# protoLoad.net
KiCad netlist of a schematic drawn in EAGLE
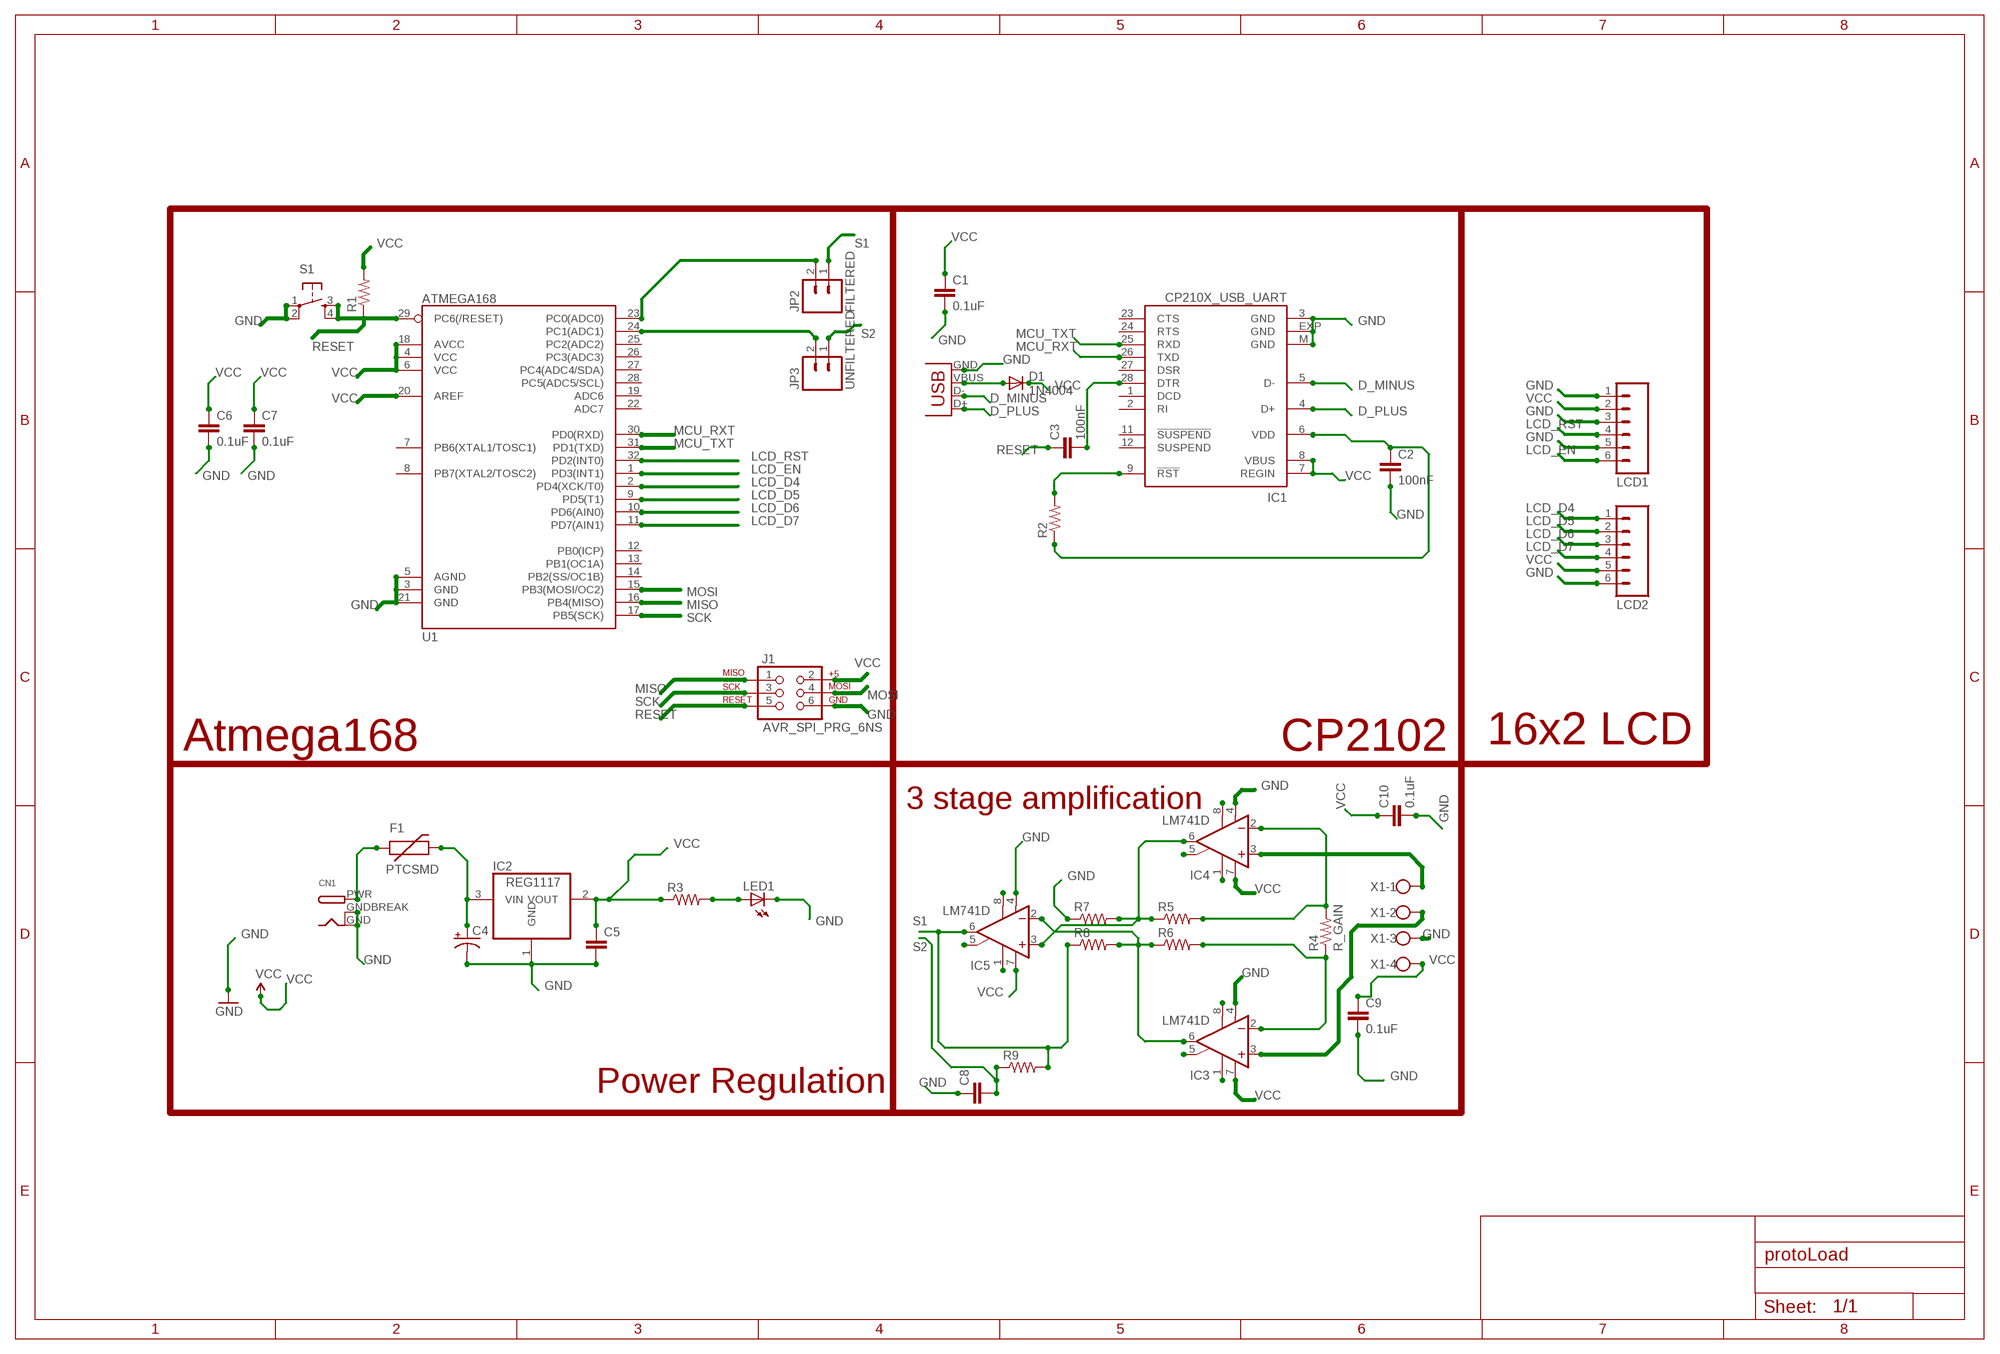
[diagram p0: schematic, sheet 1]

(export (version "E")
  (design (tool "Eeschema 10.0.6"))
  (components
    (comp (ref "C1")
      (value "0.1uF")
      (footprint "eagle-import:0805")
      (libsource (lib "eagle-import") (part "CAP0805"))
    )
    (comp (ref "C2")
      (value "100nF")
      (footprint "eagle-import:0805")
      (libsource (lib "eagle-import") (part "CAP0805"))
    )
    (comp (ref "C3")
      (value "100nF")
      (footprint "eagle-import:0805")
      (libsource (lib "eagle-import") (part "CAP0805"))
    )
    (comp (ref "C4")
      (value "CAP_POL7343")
      (footprint "eagle-import:EIA7343")
      (libsource (lib "eagle-import") (part "CAP_POL7343"))
    )
    (comp (ref "C5")
      (value "CAP0805")
      (footprint "eagle-import:0805")
      (libsource (lib "eagle-import") (part "CAP0805"))
    )
    (comp (ref "C6")
      (value "0.1uF")
      (footprint "eagle-import:0805")
      (libsource (lib "eagle-import") (part "CAP0805"))
    )
    (comp (ref "C7")
      (value "0.1uF")
      (footprint "eagle-import:0805")
      (libsource (lib "eagle-import") (part "CAP0805"))
    )
    (comp (ref "C8")
      (value "CAP0805")
      (footprint "eagle-import:0805")
      (libsource (lib "eagle-import") (part "CAP0805"))
    )
    (comp (ref "C9")
      (value "0.1uF")
      (footprint "eagle-import:0805")
      (libsource (lib "eagle-import") (part "CAP0805"))
    )
    (comp (ref "C10")
      (value "0.1uF")
      (footprint "eagle-import:0805")
      (libsource (lib "eagle-import") (part "CAP0805"))
    )
    (comp (ref "CN1")
      (value "DCBARRELPTH")
      (footprint "eagle-import:DCJACK_2MM_PTH")
      (libsource (lib "eagle-import") (part "DCBARRELPTH"))
    )
    (comp (ref "D1")
      (value "1N4004")
      (footprint "eagle-import:SMA-DIODE_ALT")
      (libsource (lib "eagle-import") (part "DIODESMA-ALT"))
    )
    (comp (ref "F1")
      (value "PTCSMD")
      (footprint "eagle-import:PTC-1206")
      (libsource (lib "eagle-import") (part "PTCSMD"))
    )
    (comp (ref "IC1")
      (value "CP210X_USB_UART")
      (footprint "eagle-import:MLP28")
      (libsource (lib "eagle-import") (part "CP210X_USB_UART"))
    )
    (comp (ref "IC2")
      (value "REG1117")
      (footprint "eagle-import:SOT223")
      (libsource (lib "eagle-import") (part "REG1117"))
    )
    (comp (ref "IC3")
      (value "LM741D")
      (footprint "eagle-import:SO08")
      (libsource (lib "eagle-import") (part "741DLM"))
    )
    (comp (ref "IC4")
      (value "LM741D")
      (footprint "eagle-import:SO08")
      (libsource (lib "eagle-import") (part "741DLM"))
    )
    (comp (ref "IC5")
      (value "LM741D")
      (footprint "eagle-import:SO08")
      (libsource (lib "eagle-import") (part "741DLM"))
    )
    (comp (ref "J1")
      (value "AVR_SPI_PRG_6NS")
      (footprint "eagle-import:2X3-NS")
      (libsource (lib "eagle-import") (part "AVR_SPI_PRG_6NS"))
    )
    (comp (ref "JP1")
      (value "USBSMD")
      (footprint "eagle-import:USB-MINIB")
      (libsource (lib "eagle-import") (part "USBSMD"))
    )
    (comp (ref "JP2")
      (value "FILTERED")
      (footprint "eagle-import:1X02_LONGPADS")
      (libsource (lib "eagle-import") (part "M02PTH3"))
    )
    (comp (ref "JP3")
      (value "UNFILTERED")
      (footprint "eagle-import:1X02_LONGPADS")
      (libsource (lib "eagle-import") (part "M02PTH3"))
    )
    (comp (ref "LCD1")
      (value "M06LONGPADS")
      (footprint "eagle-import:1X06_LONGPADS")
      (libsource (lib "eagle-import") (part "M06LONGPADS"))
    )
    (comp (ref "LCD2")
      (value "M06LONGPADS")
      (footprint "eagle-import:1X06_LONGPADS")
      (libsource (lib "eagle-import") (part "M06LONGPADS"))
    )
    (comp (ref "LED1")
      (value "LEDCHIPLED_1206")
      (footprint "eagle-import:CHIPLED_1206")
      (libsource (lib "eagle-import") (part "LEDCHIPLED_1206"))
    )
    (comp (ref "R1")
      (value "RESISTOR0805-RES")
      (footprint "eagle-import:0805")
      (libsource (lib "eagle-import") (part "SparkFun-Resistors_RESISTOR0805-RES"))
    )
    (comp (ref "R2")
      (value "RESISTOR0805-RES")
      (footprint "eagle-import:0805")
      (libsource (lib "eagle-import") (part "RESISTOR0805-RES"))
    )
    (comp (ref "R3")
      (value "RESISTOR0805-RES")
      (footprint "eagle-import:0805")
      (libsource (lib "eagle-import") (part "SparkFun-Resistors_RESISTOR0805-RES"))
    )
    (comp (ref "R4")
      (value "R_GAIN")
      (footprint "eagle-import:0805")
      (libsource (lib "eagle-import") (part "SparkFun-Resistors_RESISTOR0805-RES"))
    )
    (comp (ref "R5")
      (value "RESISTOR0805-RES")
      (footprint "eagle-import:0805")
      (libsource (lib "eagle-import") (part "SparkFun-Resistors_RESISTOR0805-RES"))
    )
    (comp (ref "R6")
      (value "RESISTOR0805-RES")
      (footprint "eagle-import:0805")
      (libsource (lib "eagle-import") (part "SparkFun-Resistors_RESISTOR0805-RES"))
    )
    (comp (ref "R7")
      (value "RESISTOR0805-RES")
      (footprint "eagle-import:0805")
      (libsource (lib "eagle-import") (part "SparkFun-Resistors_RESISTOR0805-RES"))
    )
    (comp (ref "R8")
      (value "RESISTOR0805-RES")
      (footprint "eagle-import:0805")
      (libsource (lib "eagle-import") (part "SparkFun-Resistors_RESISTOR0805-RES"))
    )
    (comp (ref "R9")
      (value "RESISTOR0805-RES")
      (footprint "eagle-import:0805")
      (libsource (lib "eagle-import") (part "SparkFun-Resistors_RESISTOR0805-RES"))
    )
    (comp (ref "S1")
      (value "TAC_SWITCHSMD")
      (footprint "eagle-import:TACTILE_SWITCH_SMD")
      (libsource (lib "eagle-import") (part "TAC_SWITCHSMD"))
    )
    (comp (ref "U1")
      (value "ATMEGA168")
      (footprint "eagle-import:TQFP32-08")
      (libsource (lib "eagle-import") (part "ATMEGA168"))
    )
    (comp (ref "X1")
      (value "W237-4")
      (footprint "eagle-import:W237-4")
      (libsource (lib "eagle-import") (part "W237-4"))
    )
  )
  (nets
    (net (code "1") (name "/D_MINUS") (class "Default")
      (node (ref "IC1") (pin "5") (pinfunction "D-_5") (pintype "bidirectional"))
      (node (ref "JP1") (pin "D-") (pinfunction "D-_D-") (pintype "bidirectional"))
    )
    (net (code "2") (name "/D_PLUS") (class "Default")
      (node (ref "IC1") (pin "4") (pinfunction "D+_4") (pintype "bidirectional"))
      (node (ref "JP1") (pin "D+") (pinfunction "D+_D+") (pintype "bidirectional"))
    )
    (net (code "3") (name "/LCD_D4") (class "Default")
      (node (ref "LCD2") (pin "1") (pinfunction "1_1") (pintype "passive"))
      (node (ref "U1") (pin "2") (pinfunction "PD4(XCK/T0)_2") (pintype "bidirectional"))
    )
    (net (code "4") (name "/LCD_D5") (class "Default")
      (node (ref "LCD2") (pin "2") (pinfunction "2_2") (pintype "passive"))
      (node (ref "U1") (pin "9") (pinfunction "PD5(T1)_9") (pintype "bidirectional"))
    )
    (net (code "5") (name "/LCD_D6") (class "Default")
      (node (ref "LCD2") (pin "3") (pinfunction "3_3") (pintype "passive"))
      (node (ref "U1") (pin "10") (pinfunction "PD6(AIN0)_10") (pintype "bidirectional"))
    )
    (net (code "6") (name "/LCD_D7") (class "Default")
      (node (ref "LCD2") (pin "4") (pinfunction "4_4") (pintype "passive"))
      (node (ref "U1") (pin "11") (pinfunction "PD7(AIN1)_11") (pintype "bidirectional"))
    )
    (net (code "7") (name "/LCD_EN") (class "Default")
      (node (ref "LCD1") (pin "6") (pinfunction "6_6") (pintype "passive"))
      (node (ref "U1") (pin "1") (pinfunction "PD3(INT1)_1") (pintype "bidirectional"))
    )
    (net (code "8") (name "/LCD_RST") (class "Default")
      (node (ref "LCD1") (pin "4") (pinfunction "4_4") (pintype "passive"))
      (node (ref "U1") (pin "32") (pinfunction "PD2(INT0)_32") (pintype "bidirectional"))
    )
    (net (code "9") (name "/MCU_RXT") (class "Default")
      (node (ref "IC1") (pin "26") (pinfunction "TXD_26") (pintype "output"))
      (node (ref "U1") (pin "30") (pinfunction "PD0(RXD)_30") (pintype "bidirectional"))
    )
    (net (code "10") (name "/MCU_TXT") (class "Default")
      (node (ref "IC1") (pin "25") (pinfunction "RXD_25") (pintype "input"))
      (node (ref "U1") (pin "31") (pinfunction "PD1(TXD)_31") (pintype "bidirectional"))
    )
    (net (code "11") (name "/MISO") (class "Default")
      (node (ref "J1") (pin "1") (pinfunction "1_1") (pintype "passive"))
      (node (ref "U1") (pin "16") (pinfunction "PB4(MISO)_16") (pintype "bidirectional"))
    )
    (net (code "12") (name "/MOSI") (class "Default")
      (node (ref "J1") (pin "4") (pinfunction "4_4") (pintype "passive"))
      (node (ref "U1") (pin "15") (pinfunction "PB3(MOSI/OC2)_15") (pintype "bidirectional"))
    )
    (net (code "13") (name "/RESET") (class "Default")
      (node (ref "C3") (pin "1") (pinfunction "1_1") (pintype "passive"))
      (node (ref "J1") (pin "5") (pinfunction "5_5") (pintype "passive"))
      (node (ref "R1") (pin "1") (pinfunction "1_1") (pintype "passive"))
      (node (ref "S1") (pin "3") (pinfunction "3_3") (pintype "passive"))
      (node (ref "S1") (pin "4") (pinfunction "4_4") (pintype "passive"))
      (node (ref "U1") (pin "29") (pinfunction "PC6(/RESET)_29") (pintype "bidirectional"))
    )
    (net (code "14") (name "/S1") (class "Default")
      (node (ref "IC5") (pin "6") (pinfunction "OUT_6") (pintype "output"))
      (node (ref "JP2") (pin "1") (pinfunction "1_1") (pintype "passive"))
      (node (ref "R8") (pin "1") (pinfunction "1_1") (pintype "passive"))
      (node (ref "R9") (pin "2") (pinfunction "2_2") (pintype "passive"))
    )
    (net (code "15") (name "/S2") (class "Default")
      (node (ref "C8") (pin "2") (pinfunction "2_2") (pintype "passive"))
      (node (ref "JP3") (pin "1") (pinfunction "1_1") (pintype "passive"))
      (node (ref "R9") (pin "1") (pinfunction "1_1") (pintype "passive"))
    )
    (net (code "16") (name "/SCK") (class "Default")
      (node (ref "J1") (pin "3") (pinfunction "3_3") (pintype "passive"))
      (node (ref "U1") (pin "17") (pinfunction "PB5(SCK)_17") (pintype "bidirectional"))
    )
    (net (code "17") (name "GND") (class "Default")
      (node (ref "C1") (pin "2") (pinfunction "2_2") (pintype "passive"))
      (node (ref "C10") (pin "2") (pinfunction "2_2") (pintype "passive"))
      (node (ref "C2") (pin "2") (pinfunction "2_2") (pintype "passive"))
      (node (ref "C4") (pin "C") (pinfunction "-_C") (pintype "passive"))
      (node (ref "C5") (pin "2") (pinfunction "2_2") (pintype "passive"))
      (node (ref "C6") (pin "2") (pinfunction "2_2") (pintype "passive"))
      (node (ref "C7") (pin "2") (pinfunction "2_2") (pintype "passive"))
      (node (ref "C8") (pin "1") (pinfunction "1_1") (pintype "passive"))
      (node (ref "C9") (pin "2") (pinfunction "2_2") (pintype "passive"))
      (node (ref "CN1") (pin "GND") (pinfunction "GND_GND") (pintype "power_in"))
      (node (ref "CN1") (pin "GNDBREAK") (pinfunction "GNDBREAK_GNDBREAK") (pintype "power_in"))
      (node (ref "IC1") (pin "3") (pinfunction "GND_3") (pintype "power_in"))
      (node (ref "IC1") (pin "EXP") (pinfunction "GND_EXP") (pintype "power_in"))
      (node (ref "IC1") (pin "M") (pinfunction "GND_M") (pintype "power_in"))
      (node (ref "IC2") (pin "1") (pinfunction "GND_1") (pintype "power_in"))
      (node (ref "IC3") (pin "4") (pinfunction "V-_4") (pintype "power_in"))
      (node (ref "IC4") (pin "4") (pinfunction "V-_4") (pintype "power_in"))
      (node (ref "IC5") (pin "4") (pinfunction "V-_4") (pintype "power_in"))
      (node (ref "J1") (pin "6") (pinfunction "6_6") (pintype "passive"))
      (node (ref "JP1") (pin "GND") (pinfunction "GND_GND") (pintype "bidirectional"))
      (node (ref "LCD1") (pin "1") (pinfunction "1_1") (pintype "passive"))
      (node (ref "LCD1") (pin "3") (pinfunction "3_3") (pintype "passive"))
      (node (ref "LCD1") (pin "5") (pinfunction "5_5") (pintype "passive"))
      (node (ref "LCD2") (pin "6") (pinfunction "6_6") (pintype "passive"))
      (node (ref "LED1") (pin "C") (pinfunction "C_C") (pintype "passive"))
      (node (ref "R7") (pin "1") (pinfunction "1_1") (pintype "passive"))
      (node (ref "S1") (pin "1") (pinfunction "1_1") (pintype "passive"))
      (node (ref "S1") (pin "2") (pinfunction "2_2") (pintype "passive"))
      (node (ref "U1") (pin "21") (pinfunction "GND_21") (pintype "bidirectional"))
      (node (ref "U1") (pin "3") (pinfunction "GND_3") (pintype "bidirectional"))
      (node (ref "U1") (pin "5") (pinfunction "AGND_5") (pintype "bidirectional"))
      (node (ref "X1") (pin "3") (pinfunction "KL_3") (pintype "passive"))
    )
    (net (code "18") (name "Net-(C4-+)") (class "Default")
      (node (ref "C4") (pin "A") (pinfunction "+_A") (pintype "passive"))
      (node (ref "F1") (pin "2") (pinfunction "2_2") (pintype "bidirectional"))
      (node (ref "IC2") (pin "3") (pinfunction "VIN_3") (pintype "input"))
    )
    (net (code "19") (name "Net-(CN1-PadPWR)") (class "Default")
      (node (ref "CN1") (pin "PWR") (pinfunction "PWR_PWR") (pintype "power_in"))
      (node (ref "F1") (pin "1") (pinfunction "1_1") (pintype "bidirectional"))
    )
    (net (code "20") (name "Net-(D1-PadA)") (class "Default")
      (node (ref "D1") (pin "A") (pinfunction "A_A") (pintype "passive"))
      (node (ref "JP1") (pin "VBUS") (pinfunction "VBUS_VBUS") (pintype "bidirectional"))
    )
    (net (code "21") (name "Net-(IC1-DTR)") (class "Default")
      (node (ref "C3") (pin "2") (pinfunction "2_2") (pintype "passive"))
      (node (ref "IC1") (pin "28") (pinfunction "DTR_28") (pintype "output"))
    )
    (net (code "22") (name "Net-(IC1-VDD)") (class "Default")
      (node (ref "C2") (pin "1") (pinfunction "1_1") (pintype "passive"))
      (node (ref "IC1") (pin "6") (pinfunction "VDD_6") (pintype "power_in"))
      (node (ref "R2") (pin "1") (pinfunction "1_1") (pintype "passive"))
    )
    (net (code "23") (name "Net-(IC1-~{RST})") (class "Default")
      (node (ref "IC1") (pin "9") (pinfunction "~{RST}_9") (pintype "bidirectional"))
      (node (ref "R2") (pin "2") (pinfunction "2_2") (pintype "passive"))
    )
    (net (code "24") (name "Net-(IC3-+IN)") (class "Default")
      (node (ref "IC3") (pin "3") (pinfunction "+IN_3") (pintype "input"))
      (node (ref "X1") (pin "2") (pinfunction "KL_2") (pintype "passive"))
    )
    (net (code "25") (name "Net-(IC3--IN)") (class "Default")
      (node (ref "IC3") (pin "2") (pinfunction "-IN_2") (pintype "input"))
      (node (ref "R4") (pin "1") (pinfunction "1_1") (pintype "passive"))
      (node (ref "R6") (pin "2") (pinfunction "2_2") (pintype "passive"))
    )
    (net (code "26") (name "Net-(IC3-OUT)") (class "Default")
      (node (ref "IC3") (pin "6") (pinfunction "OUT_6") (pintype "output"))
      (node (ref "IC5") (pin "2") (pinfunction "-IN_2") (pintype "input"))
      (node (ref "R6") (pin "1") (pinfunction "1_1") (pintype "passive"))
      (node (ref "R8") (pin "2") (pinfunction "2_2") (pintype "passive"))
    )
    (net (code "27") (name "Net-(IC4-+IN)") (class "Default")
      (node (ref "IC4") (pin "3") (pinfunction "+IN_3") (pintype "input"))
      (node (ref "X1") (pin "1") (pinfunction "KL_1") (pintype "passive"))
    )
    (net (code "28") (name "Net-(IC4--IN)") (class "Default")
      (node (ref "IC4") (pin "2") (pinfunction "-IN_2") (pintype "input"))
      (node (ref "R4") (pin "2") (pinfunction "2_2") (pintype "passive"))
      (node (ref "R5") (pin "2") (pinfunction "2_2") (pintype "passive"))
    )
    (net (code "29") (name "Net-(IC4-OUT)") (class "Default")
      (node (ref "IC4") (pin "6") (pinfunction "OUT_6") (pintype "output"))
      (node (ref "IC5") (pin "3") (pinfunction "+IN_3") (pintype "input"))
      (node (ref "R5") (pin "1") (pinfunction "1_1") (pintype "passive"))
      (node (ref "R7") (pin "2") (pinfunction "2_2") (pintype "passive"))
    )
    (net (code "30") (name "Net-(LED1-PadA)") (class "Default")
      (node (ref "LED1") (pin "A") (pinfunction "A_A") (pintype "passive"))
      (node (ref "R3") (pin "2") (pinfunction "2_2") (pintype "passive"))
    )
    (net (code "31") (name "Net-(U1-PC0(ADC0))") (class "Default")
      (node (ref "JP2") (pin "2") (pinfunction "2_2") (pintype "passive"))
      (node (ref "U1") (pin "23") (pinfunction "PC0(ADC0)_23") (pintype "bidirectional"))
    )
    (net (code "32") (name "Net-(U1-PC1(ADC1))") (class "Default")
      (node (ref "JP3") (pin "2") (pinfunction "2_2") (pintype "passive"))
      (node (ref "U1") (pin "24") (pinfunction "PC1(ADC1)_24") (pintype "bidirectional"))
    )
    (net (code "33") (name "VCC") (class "Default")
      (node (ref "C1") (pin "1") (pinfunction "1_1") (pintype "passive"))
      (node (ref "C10") (pin "1") (pinfunction "1_1") (pintype "passive"))
      (node (ref "C5") (pin "1") (pinfunction "1_1") (pintype "passive"))
      (node (ref "C6") (pin "1") (pinfunction "1_1") (pintype "passive"))
      (node (ref "C7") (pin "1") (pinfunction "1_1") (pintype "passive"))
      (node (ref "C9") (pin "1") (pinfunction "1_1") (pintype "passive"))
      (node (ref "D1") (pin "C") (pinfunction "C_C") (pintype "passive"))
      (node (ref "IC1") (pin "7") (pinfunction "REGIN_7") (pintype "passive"))
      (node (ref "IC1") (pin "8") (pinfunction "VBUS_8") (pintype "input"))
      (node (ref "IC2") (pin "2") (pinfunction "VOUT_2") (pintype "output"))
      (node (ref "IC3") (pin "7") (pinfunction "V+_7") (pintype "power_in"))
      (node (ref "IC4") (pin "7") (pinfunction "V+_7") (pintype "power_in"))
      (node (ref "IC5") (pin "7") (pinfunction "V+_7") (pintype "power_in"))
      (node (ref "J1") (pin "2") (pinfunction "2_2") (pintype "passive"))
      (node (ref "LCD1") (pin "2") (pinfunction "2_2") (pintype "passive"))
      (node (ref "LCD2") (pin "5") (pinfunction "5_5") (pintype "passive"))
      (node (ref "R1") (pin "2") (pinfunction "2_2") (pintype "passive"))
      (node (ref "R3") (pin "1") (pinfunction "1_1") (pintype "passive"))
      (node (ref "U1") (pin "18") (pinfunction "AVCC_18") (pintype "bidirectional"))
      (node (ref "U1") (pin "20") (pinfunction "AREF_20") (pintype "bidirectional"))
      (node (ref "U1") (pin "4") (pinfunction "VCC_4") (pintype "bidirectional"))
      (node (ref "U1") (pin "6") (pinfunction "VCC_6") (pintype "bidirectional"))
      (node (ref "X1") (pin "4") (pinfunction "KL_4") (pintype "passive"))
    )
    (net (code "34") (name "unconnected-(IC1-CTS-Pad23)") (class "Default")
      (node (ref "IC1") (pin "23") (pinfunction "CTS_23") (pintype "input"))
    )
    (net (code "35") (name "unconnected-(IC1-DCD-Pad1)") (class "Default")
      (node (ref "IC1") (pin "1") (pinfunction "DCD_1") (pintype "input"))
    )
    (net (code "36") (name "unconnected-(IC1-DSR-Pad27)") (class "Default")
      (node (ref "IC1") (pin "27") (pinfunction "DSR_27") (pintype "input"))
    )
    (net (code "37") (name "unconnected-(IC1-RI-Pad2)") (class "Default")
      (node (ref "IC1") (pin "2") (pinfunction "RI_2") (pintype "input"))
    )
    (net (code "38") (name "unconnected-(IC1-RTS-Pad24)") (class "Default")
      (node (ref "IC1") (pin "24") (pinfunction "RTS_24") (pintype "output"))
    )
    (net (code "39") (name "unconnected-(IC1-SUSPEND-Pad12)") (class "Default")
      (node (ref "IC1") (pin "12") (pinfunction "SUSPEND_12") (pintype "output"))
    )
    (net (code "40") (name "unconnected-(IC1-~{SUSPEND}-Pad11)") (class "Default")
      (node (ref "IC1") (pin "11") (pinfunction "~{SUSPEND}_11") (pintype "output"))
    )
    (net (code "41") (name "unconnected-(IC3-ON1-Pad1)") (class "Default")
      (node (ref "IC3") (pin "1") (pinfunction "ON1_1") (pintype "passive"))
    )
    (net (code "42") (name "unconnected-(IC3-ON2-Pad5)") (class "Default")
      (node (ref "IC3") (pin "5") (pinfunction "ON2_5") (pintype "passive"))
    )
    (net (code "43") (name "unconnected-(IC3-OPT-Pad8)") (class "Default")
      (node (ref "IC3") (pin "8") (pinfunction "OPT_8") (pintype "passive"))
    )
    (net (code "44") (name "unconnected-(IC4-ON1-Pad1)") (class "Default")
      (node (ref "IC4") (pin "1") (pinfunction "ON1_1") (pintype "passive"))
    )
    (net (code "45") (name "unconnected-(IC4-ON2-Pad5)") (class "Default")
      (node (ref "IC4") (pin "5") (pinfunction "ON2_5") (pintype "passive"))
    )
    (net (code "46") (name "unconnected-(IC4-OPT-Pad8)") (class "Default")
      (node (ref "IC4") (pin "8") (pinfunction "OPT_8") (pintype "passive"))
    )
    (net (code "47") (name "unconnected-(IC5-ON1-Pad1)") (class "Default")
      (node (ref "IC5") (pin "1") (pinfunction "ON1_1") (pintype "passive"))
    )
    (net (code "48") (name "unconnected-(IC5-ON2-Pad5)") (class "Default")
      (node (ref "IC5") (pin "5") (pinfunction "ON2_5") (pintype "passive"))
    )
    (net (code "49") (name "unconnected-(IC5-OPT-Pad8)") (class "Default")
      (node (ref "IC5") (pin "8") (pinfunction "OPT_8") (pintype "passive"))
    )
    (net (code "50") (name "unconnected-(U1-ADC6-Pad19)") (class "Default")
      (node (ref "U1") (pin "19") (pinfunction "ADC6_19") (pintype "bidirectional"))
    )
    (net (code "51") (name "unconnected-(U1-ADC7-Pad22)") (class "Default")
      (node (ref "U1") (pin "22") (pinfunction "ADC7_22") (pintype "bidirectional"))
    )
    (net (code "52") (name "unconnected-(U1-PB0(ICP)-Pad12)") (class "Default")
      (node (ref "U1") (pin "12") (pinfunction "PB0(ICP)_12") (pintype "bidirectional"))
    )
    (net (code "53") (name "unconnected-(U1-PB1(OC1A)-Pad13)") (class "Default")
      (node (ref "U1") (pin "13") (pinfunction "PB1(OC1A)_13") (pintype "bidirectional"))
    )
    (net (code "54") (name "unconnected-(U1-PB2(SS{slash}OC1B)-Pad14)") (class "Default")
      (node (ref "U1") (pin "14") (pinfunction "PB2(SS/OC1B)_14") (pintype "bidirectional"))
    )
    (net (code "55") (name "unconnected-(U1-PB6(XTAL1{slash}TOSC1)-Pad7)") (class "Default")
      (node (ref "U1") (pin "7") (pinfunction "PB6(XTAL1/TOSC1)_7") (pintype "bidirectional"))
    )
    (net (code "56") (name "unconnected-(U1-PB7(XTAL2{slash}TOSC2)-Pad8)") (class "Default")
      (node (ref "U1") (pin "8") (pinfunction "PB7(XTAL2/TOSC2)_8") (pintype "bidirectional"))
    )
    (net (code "57") (name "unconnected-(U1-PC2(ADC2)-Pad25)") (class "Default")
      (node (ref "U1") (pin "25") (pinfunction "PC2(ADC2)_25") (pintype "bidirectional"))
    )
    (net (code "58") (name "unconnected-(U1-PC3(ADC3)-Pad26)") (class "Default")
      (node (ref "U1") (pin "26") (pinfunction "PC3(ADC3)_26") (pintype "bidirectional"))
    )
    (net (code "59") (name "unconnected-(U1-PC4(ADC4{slash}SDA)-Pad27)") (class "Default")
      (node (ref "U1") (pin "27") (pinfunction "PC4(ADC4/SDA)_27") (pintype "bidirectional"))
    )
    (net (code "60") (name "unconnected-(U1-PC5(ADC5{slash}SCL)-Pad28)") (class "Default")
      (node (ref "U1") (pin "28") (pinfunction "PC5(ADC5/SCL)_28") (pintype "bidirectional"))
    )
  )
)
